# DCDC.net
KiCad netlist of a schematic drawn in Altium Designer
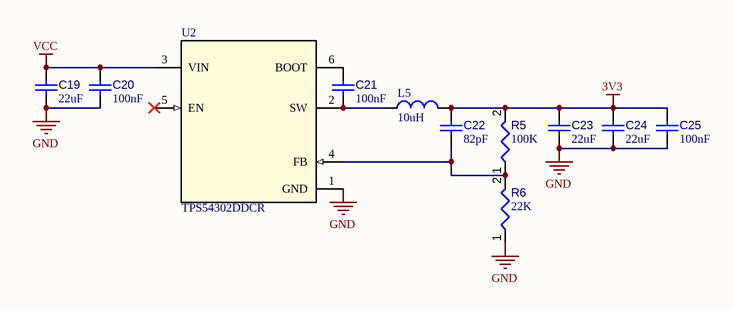
[diagram p0: DCDC.SchDoc]

(export (version "E")
  (design (tool "Eeschema 10.0.6"))
  (components
    (comp (ref "C19")
      (value "22uF")
      (footprint "CAPC2012X14L")
      (description "Non-Polarized Capacitor Symbol")
      (fields (field (name "TOLERANCE") "20%") (field (name "Comment") "CL21A226MAQNNNE"))
      (libsource (lib "Database") (part "Non-Polarized Capacitor Sym"))
    )
    (comp (ref "C20")
      (value "100nF")
      (footprint "CAPC1005X55X25LL05T05")
      (description "Non-Polarized Capacitor Symbol")
      (fields (field (name "TOLERANCE") "10%") (field (name "Comment") "CL05B104KB5NNNC"))
      (libsource (lib "Database") (part "Non-Polarized Capacitor Sym"))
    )
    (comp (ref "C21")
      (value "100nF")
      (footprint "CAPC1005X55X25LL05T05")
      (description "Non-Polarized Capacitor Symbol")
      (fields (field (name "TOLERANCE") "10%") (field (name "Comment") "CL05B104KB5NNNC"))
      (libsource (lib "Database") (part "Non-Polarized Capacitor Sym"))
    )
    (comp (ref "C22")
      (value "82pF")
      (footprint "CAPC1005X55X25LL05T05")
      (description "Non-Polarized Capacitor Symbol")
      (fields (field (name "TOLERANCE") "5%") (field (name "Comment") "CL05C820JB5NNNC"))
      (libsource (lib "Database") (part "Non-Polarized Capacitor Sym"))
    )
    (comp (ref "C23")
      (value "22uF")
      (footprint "CAPC1608X87X35LL15T15")
      (description "Non-Polarized Capacitor Symbol")
      (fields (field (name "TOLERANCE") "20%") (field (name "Comment") "CL10A226MP8NUNE"))
      (libsource (lib "Database") (part "Non-Polarized Capacitor Sym"))
    )
    (comp (ref "C24")
      (value "22uF")
      (footprint "CAPC1608X87X35LL15T15")
      (description "Non-Polarized Capacitor Symbol")
      (fields (field (name "TOLERANCE") "20%") (field (name "Comment") "CL10A226MP8NUNE"))
      (libsource (lib "Database") (part "Non-Polarized Capacitor Sym"))
    )
    (comp (ref "C25")
      (value "100nF")
      (footprint "CAPC1608X87X35LL15T15")
      (description "Non-Polarized Capacitor Symbol")
      (fields (field (name "TOLERANCE") "5%") (field (name "Comment") "CL10B104JB8NNNC"))
      (libsource (lib "Database") (part "Non-Polarized Capacitor Sym"))
    )
    (comp (ref "L5")
      (value "10uH")
      (footprint "INDP5050X42L")
      (fields (field (name "Comment") "SWPA5040S100MT"))
      (libsource (lib "Database") (part "2 Terminal Inductor"))
    )
    (comp (ref "R5")
      (value "100K")
      (footprint "RESC1005X40X25LL05T05")
      (description "Chip Resistor, 100K Ohm, +/- 1%, 0.063 W, -55 to 155 degC, 0402 (1005 Metric)")
      (fields (field (name "Comment") "100K 0402"))
      (libsource (lib "Database") (part "Chip Resistor"))
    )
    (comp (ref "R6")
      (value "22K")
      (footprint "RESC1005X40X25LL05T05")
      (description "0402 Chip Resistor")
      (fields (field (name "Comment") "22K 0402"))
      (libsource (lib "Database") (part "Chip Resistor"))
    )
    (comp (ref "U2")
      (value "TPS54302DDCR")
      (footprint "TSOP-6_L")
      (description "4.5-V to 28-V Input, 3-A Output, EMI-Friendly Synchronous Step-Down Converter")
      (libsource (lib "Database") (part "TPS54302DDCR"))
    )
  )
  (nets
    (net (code "1") (name "3V3") (class "Default")
      (node (ref "C22") (pin "2") (pinfunction "2_2") (pintype "passive"))
      (node (ref "C23") (pin "2") (pinfunction "2_2") (pintype "passive"))
      (node (ref "C24") (pin "2") (pinfunction "2_2") (pintype "passive"))
      (node (ref "C25") (pin "2") (pinfunction "2_2") (pintype "passive"))
      (node (ref "L5") (pin "2") (pinfunction "2_2") (pintype "passive"))
      (node (ref "R5") (pin "2") (pinfunction "2_2") (pintype "passive"))
    )
    (net (code "2") (name "GND") (class "Default")
      (node (ref "C19") (pin "1") (pinfunction "1_1") (pintype "passive"))
      (node (ref "C20") (pin "1") (pinfunction "1_1") (pintype "passive"))
      (node (ref "C23") (pin "1") (pinfunction "1_1") (pintype "passive"))
      (node (ref "C24") (pin "1") (pinfunction "1_1") (pintype "passive"))
      (node (ref "C25") (pin "1") (pinfunction "1_1") (pintype "passive"))
      (node (ref "R6") (pin "1") (pinfunction "1_1") (pintype "passive"))
      (node (ref "U2") (pin "1") (pinfunction "GND_1") (pintype "power_in"))
    )
    (net (code "3") (name "Net-(U2-BOOT)") (class "Default")
      (node (ref "C21") (pin "2") (pinfunction "2_2") (pintype "passive"))
      (node (ref "U2") (pin "6") (pinfunction "BOOT_6") (pintype "power_in"))
    )
    (net (code "4") (name "Net-(U2-FB)") (class "Default")
      (node (ref "C22") (pin "1") (pinfunction "1_1") (pintype "passive"))
      (node (ref "R5") (pin "1") (pinfunction "1_1") (pintype "passive"))
      (node (ref "R6") (pin "2") (pinfunction "2_2") (pintype "passive"))
      (node (ref "U2") (pin "4") (pinfunction "FB_4") (pintype "input"))
    )
    (net (code "5") (name "Net-(U2-SW)") (class "Default")
      (node (ref "C21") (pin "1") (pinfunction "1_1") (pintype "passive"))
      (node (ref "L5") (pin "1") (pinfunction "1_1") (pintype "passive"))
      (node (ref "U2") (pin "2") (pinfunction "SW_2") (pintype "power_in"))
    )
    (net (code "6") (name "VCC") (class "Default")
      (node (ref "C19") (pin "2") (pinfunction "2_2") (pintype "passive"))
      (node (ref "C20") (pin "2") (pinfunction "2_2") (pintype "passive"))
      (node (ref "U2") (pin "3") (pinfunction "VIN_3") (pintype "power_in"))
    )
    (net (code "7") (name "unconnected-(U2-EN-Pad5)") (class "Default")
      (node (ref "U2") (pin "5") (pinfunction "EN_5") (pintype "input+no_connect"))
    )
  )
)
